# Headlight_Board.net
KiCad netlist of a schematic drawn in Altium Designer
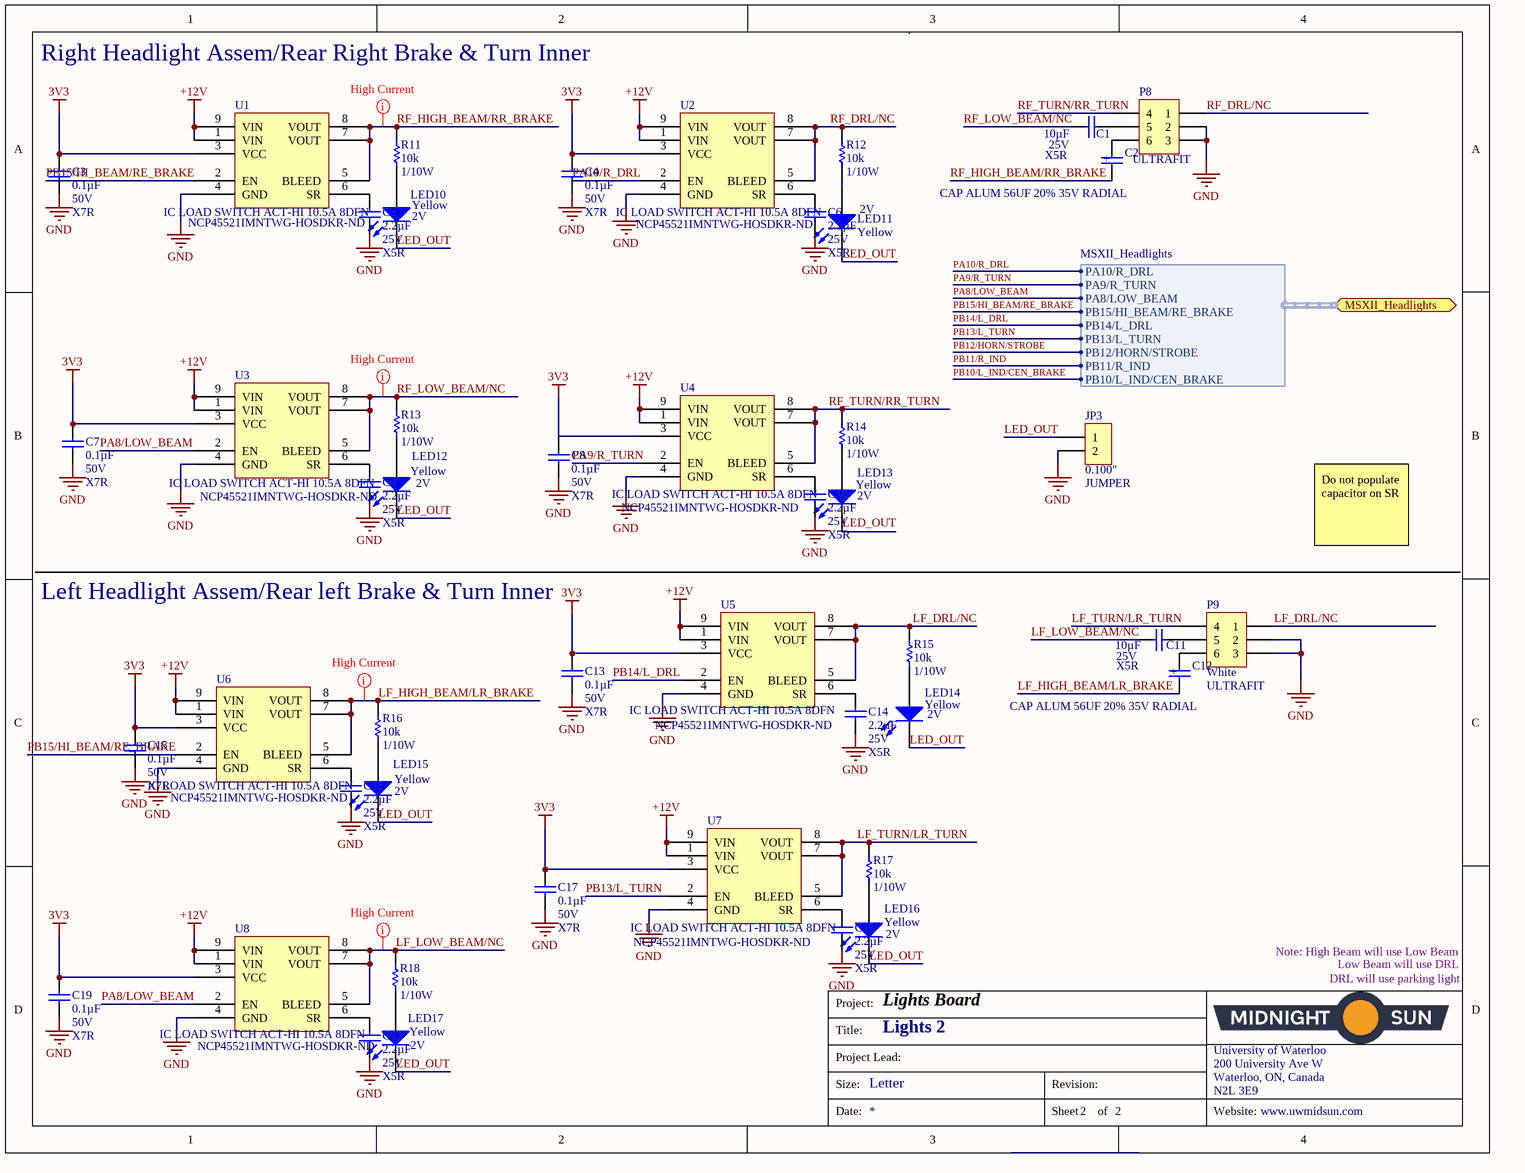
[diagram p0: Headlight_Board.SchDoc]

(export (version "E")
  (design (tool "Eeschema 10.0.6"))
  (components
    (comp (ref "C1")
      (value "CAP CER 10uF 25V 20% X5R 0603")
      (footprint "CAP, 0603")
      (description "10µF ±20% 25V Ceramic Capacitor X5R 0603 (1608 Metric)")
      (fields
        (field (name "TOLERANCE") "±20%")
        (field (name "CAPACITANCE") "10µF")
        (field (name "VOLTAGE") "25V")
        (field (name "TEMPERATURE COEFFICIENT") "X5R")
      )
      (libsource (lib "Schematic Diagrams") (part "CAP CER 10uF 25V 20% X5R 0603"))
    )
    (comp (ref "C2")
      (value "CAP ALUM 56UF 20% 35V RADIAL")
      (footprint "CAP ALUM 56UF 20% 35V RADIAL")
      (description "56µF 35V Aluminum Electrolytic Capacitors Radial, Can 1000 Hrs @ 105°C")
      (fields
        (field (name "MANUFACTURER") "Panasonic Electronic Components")
        (field (name "MANUFACTURER PART NUMBER") "EEU-FC1V560H")
      )
      (libsource (lib "Schematic Diagrams") (part "CAP ALUM 56UF 20% 35V RADIAL"))
    )
    (comp (ref "C3")
      (value "CAP CER 0.1UF 50V 10% X7R 0603")
      (footprint "CAP, 0603")
      (description "0.10µF ±10% 50V Ceramic Capacitor X7R 0603 (1608 Metric)")
      (fields
        (field (name "TOLERANCE") "±10%")
        (field (name "CAPACITANCE") "0.1µF")
        (field (name "VOLTAGE") "50V")
        (field (name "TEMPERATURE COEFFICIENT") "X7R")
      )
      (libsource (lib "Schematic Diagrams") (part "CAP CER 0.1UF 50V 10% X7R 0603"))
    )
    (comp (ref "C4")
      (value "CAP CER 0.1UF 50V 10% X7R 0603")
      (footprint "CAP, 0603")
      (description "0.10µF ±10% 50V Ceramic Capacitor X7R 0603 (1608 Metric)")
      (fields
        (field (name "TOLERANCE") "±10%")
        (field (name "CAPACITANCE") "0.1µF")
        (field (name "VOLTAGE") "50V")
        (field (name "TEMPERATURE COEFFICIENT") "X7R")
      )
      (libsource (lib "Schematic Diagrams") (part "CAP CER 0.1UF 50V 10% X7R 0603"))
    )
    (comp (ref "C5")
      (value "CAP CER 2.2UF 25V 10% X5R 0603")
      (footprint "CAP, 0603")
      (description "2.2µF ±10% 25V Ceramic Capacitor X5R 0603 (1608 Metric)")
      (fields
        (field (name "TOLERANCE") "±10%")
        (field (name "CAPACITANCE") "2.2µF")
        (field (name "VOLTAGE") "25V")
        (field (name "TEMPERATURE COEFFICIENT") "X5R")
      )
      (libsource (lib "Schematic Diagrams") (part "CAP CER 2.2UF 25V 10% X5R 0603"))
    )
    (comp (ref "C6")
      (value "CAP CER 2.2UF 25V 10% X5R 0603")
      (footprint "CAP, 0603")
      (description "2.2µF ±10% 25V Ceramic Capacitor X5R 0603 (1608 Metric)")
      (fields
        (field (name "TOLERANCE") "±10%")
        (field (name "CAPACITANCE") "2.2µF")
        (field (name "VOLTAGE") "25V")
        (field (name "TEMPERATURE COEFFICIENT") "X5R")
      )
      (libsource (lib "Schematic Diagrams") (part "CAP CER 2.2UF 25V 10% X5R 0603"))
    )
    (comp (ref "C7")
      (value "CAP CER 0.1UF 50V 10% X7R 0603")
      (footprint "CAP, 0603")
      (description "0.10µF ±10% 50V Ceramic Capacitor X7R 0603 (1608 Metric)")
      (fields
        (field (name "TOLERANCE") "±10%")
        (field (name "CAPACITANCE") "0.1µF")
        (field (name "VOLTAGE") "50V")
        (field (name "TEMPERATURE COEFFICIENT") "X7R")
      )
      (libsource (lib "Schematic Diagrams") (part "CAP CER 0.1UF 50V 10% X7R 0603"))
    )
    (comp (ref "C8")
      (value "CAP CER 0.1UF 50V 10% X7R 0603")
      (footprint "CAP, 0603")
      (description "0.10µF ±10% 50V Ceramic Capacitor X7R 0603 (1608 Metric)")
      (fields
        (field (name "TOLERANCE") "±10%")
        (field (name "CAPACITANCE") "0.1µF")
        (field (name "VOLTAGE") "50V")
        (field (name "TEMPERATURE COEFFICIENT") "X7R")
      )
      (libsource (lib "Schematic Diagrams") (part "CAP CER 0.1UF 50V 10% X7R 0603"))
    )
    (comp (ref "C9")
      (value "CAP CER 2.2UF 25V 10% X5R 0603")
      (footprint "CAP, 0603")
      (description "2.2µF ±10% 25V Ceramic Capacitor X5R 0603 (1608 Metric)")
      (fields
        (field (name "TOLERANCE") "±10%")
        (field (name "CAPACITANCE") "2.2µF")
        (field (name "VOLTAGE") "25V")
        (field (name "TEMPERATURE COEFFICIENT") "X5R")
      )
      (libsource (lib "Schematic Diagrams") (part "CAP CER 2.2UF 25V 10% X5R 0603"))
    )
    (comp (ref "C10")
      (value "CAP CER 2.2UF 25V 10% X5R 0603")
      (footprint "CAP, 0603")
      (description "2.2µF ±10% 25V Ceramic Capacitor X5R 0603 (1608 Metric)")
      (fields
        (field (name "TOLERANCE") "±10%")
        (field (name "CAPACITANCE") "2.2µF")
        (field (name "VOLTAGE") "25V")
        (field (name "TEMPERATURE COEFFICIENT") "X5R")
      )
      (libsource (lib "Schematic Diagrams") (part "CAP CER 2.2UF 25V 10% X5R 0603"))
    )
    (comp (ref "C11")
      (value "CAP CER 10uF 25V 20% X5R 0603")
      (footprint "CAP, 0603")
      (description "10µF ±20% 25V Ceramic Capacitor X5R 0603 (1608 Metric)")
      (fields
        (field (name "TOLERANCE") "±20%")
        (field (name "CAPACITANCE") "10µF")
        (field (name "VOLTAGE") "25V")
        (field (name "TEMPERATURE COEFFICIENT") "X5R")
      )
      (libsource (lib "Schematic Diagrams") (part "CAP CER 10uF 25V 20% X5R 0603"))
    )
    (comp (ref "C12")
      (value "CAP ALUM 56UF 20% 35V RADIAL")
      (footprint "CAP ALUM 56UF 20% 35V RADIAL")
      (description "56µF 35V Aluminum Electrolytic Capacitors Radial, Can 1000 Hrs @ 105°C")
      (fields
        (field (name "MANUFACTURER") "Panasonic Electronic Components")
        (field (name "MANUFACTURER PART NUMBER") "EEU-FC1V560H")
      )
      (libsource (lib "Schematic Diagrams") (part "CAP ALUM 56UF 20% 35V RADIAL"))
    )
    (comp (ref "C13")
      (value "CAP CER 0.1UF 50V 10% X7R 0603")
      (footprint "CAP, 0603")
      (description "0.10µF ±10% 50V Ceramic Capacitor X7R 0603 (1608 Metric)")
      (fields
        (field (name "TOLERANCE") "±10%")
        (field (name "CAPACITANCE") "0.1µF")
        (field (name "VOLTAGE") "50V")
        (field (name "TEMPERATURE COEFFICIENT") "X7R")
      )
      (libsource (lib "Schematic Diagrams") (part "CAP CER 0.1UF 50V 10% X7R 0603"))
    )
    (comp (ref "C14")
      (value "CAP CER 2.2UF 25V 10% X5R 0603")
      (footprint "CAP, 0603")
      (description "2.2µF ±10% 25V Ceramic Capacitor X5R 0603 (1608 Metric)")
      (fields
        (field (name "TOLERANCE") "±10%")
        (field (name "CAPACITANCE") "2.2µF")
        (field (name "VOLTAGE") "25V")
        (field (name "TEMPERATURE COEFFICIENT") "X5R")
      )
      (libsource (lib "Schematic Diagrams") (part "CAP CER 2.2UF 25V 10% X5R 0603"))
    )
    (comp (ref "C15")
      (value "CAP CER 0.1UF 50V 10% X7R 0603")
      (footprint "CAP, 0603")
      (description "0.10µF ±10% 50V Ceramic Capacitor X7R 0603 (1608 Metric)")
      (fields
        (field (name "TOLERANCE") "±10%")
        (field (name "CAPACITANCE") "0.1µF")
        (field (name "VOLTAGE") "50V")
        (field (name "TEMPERATURE COEFFICIENT") "X7R")
      )
      (libsource (lib "Schematic Diagrams") (part "CAP CER 0.1UF 50V 10% X7R 0603"))
    )
    (comp (ref "C16")
      (value "CAP CER 2.2UF 25V 10% X5R 0603")
      (footprint "CAP, 0603")
      (description "2.2µF ±10% 25V Ceramic Capacitor X5R 0603 (1608 Metric)")
      (fields
        (field (name "TOLERANCE") "±10%")
        (field (name "CAPACITANCE") "2.2µF")
        (field (name "VOLTAGE") "25V")
        (field (name "TEMPERATURE COEFFICIENT") "X5R")
      )
      (libsource (lib "Schematic Diagrams") (part "CAP CER 2.2UF 25V 10% X5R 0603"))
    )
    (comp (ref "C17")
      (value "CAP CER 0.1UF 50V 10% X7R 0603")
      (footprint "CAP, 0603")
      (description "0.10µF ±10% 50V Ceramic Capacitor X7R 0603 (1608 Metric)")
      (fields
        (field (name "TOLERANCE") "±10%")
        (field (name "CAPACITANCE") "0.1µF")
        (field (name "VOLTAGE") "50V")
        (field (name "TEMPERATURE COEFFICIENT") "X7R")
      )
      (libsource (lib "Schematic Diagrams") (part "CAP CER 0.1UF 50V 10% X7R 0603"))
    )
    (comp (ref "C18")
      (value "CAP CER 2.2UF 25V 10% X5R 0603")
      (footprint "CAP, 0603")
      (description "2.2µF ±10% 25V Ceramic Capacitor X5R 0603 (1608 Metric)")
      (fields
        (field (name "TOLERANCE") "±10%")
        (field (name "CAPACITANCE") "2.2µF")
        (field (name "VOLTAGE") "25V")
        (field (name "TEMPERATURE COEFFICIENT") "X5R")
      )
      (libsource (lib "Schematic Diagrams") (part "CAP CER 2.2UF 25V 10% X5R 0603"))
    )
    (comp (ref "C19")
      (value "CAP CER 0.1UF 50V 10% X7R 0603")
      (footprint "CAP, 0603")
      (description "0.10µF ±10% 50V Ceramic Capacitor X7R 0603 (1608 Metric)")
      (fields
        (field (name "TOLERANCE") "±10%")
        (field (name "CAPACITANCE") "0.1µF")
        (field (name "VOLTAGE") "50V")
        (field (name "TEMPERATURE COEFFICIENT") "X7R")
      )
      (libsource (lib "Schematic Diagrams") (part "CAP CER 0.1UF 50V 10% X7R 0603"))
    )
    (comp (ref "C20")
      (value "CAP CER 2.2UF 25V 10% X5R 0603")
      (footprint "CAP, 0603")
      (description "2.2µF ±10% 25V Ceramic Capacitor X5R 0603 (1608 Metric)")
      (fields
        (field (name "TOLERANCE") "±10%")
        (field (name "CAPACITANCE") "2.2µF")
        (field (name "VOLTAGE") "25V")
        (field (name "TEMPERATURE COEFFICIENT") "X5R")
      )
      (libsource (lib "Schematic Diagrams") (part "CAP CER 2.2UF 25V 10% X5R 0603"))
    )
    (comp (ref "JP3")
      (value "JUMPER")
      (footprint "CONN 2POS JUMPER 0.1\"")
      (description "2 Positions Header Connector Through Hole Gold")
      (fields
        (field (name "MANUFACTURER") "Omron Electronics Inc-EMC Div")
        (field (name "MANUFACTURER PART NUMBER") "XG8T-0231")
        (field (name "ROW SPACING - MATING") "0.100\"")
        (field (name "TYPE") "JUMPER")
      )
      (libsource (lib "Schematic Diagrams") (part "CONN 2POS JUMPER 0.1{dblquote}"))
    )
    (comp (ref "LED10")
      (value "LED YELLOW CLEAR 2.1V 0603")
      (footprint "LED_0603")
      (description "Yellow 590nm LED Indication - Discrete 2V 0603 (1608 Metric)")
      (fields
        (field (name "MANUFACTURER") "Wurth Electronics Inc.")
        (field (name "MANUFACTURER PART NUMBER") "150060YS75000")
        (field (name "COLOR") "Yellow")
        (field (name "VOLTAGE - FORWARD (VF) (TYP)") "2V")
      )
      (libsource (lib "Schematic Diagrams") (part "LED YELLOW CLEAR 2.1V 0603"))
    )
    (comp (ref "LED11")
      (value "LED YELLOW CLEAR 2.1V 0603")
      (footprint "LED_0603")
      (description "Yellow 590nm LED Indication - Discrete 2V 0603 (1608 Metric)")
      (fields
        (field (name "MANUFACTURER") "Wurth Electronics Inc.")
        (field (name "MANUFACTURER PART NUMBER") "150060YS75000")
        (field (name "COLOR") "Yellow")
        (field (name "VOLTAGE - FORWARD (VF) (TYP)") "2V")
      )
      (libsource (lib "Schematic Diagrams") (part "LED YELLOW CLEAR 2.1V 0603"))
    )
    (comp (ref "LED12")
      (value "LED YELLOW CLEAR 2.1V 0603")
      (footprint "LED_0603")
      (description "Yellow 590nm LED Indication - Discrete 2V 0603 (1608 Metric)")
      (fields
        (field (name "MANUFACTURER") "Wurth Electronics Inc.")
        (field (name "MANUFACTURER PART NUMBER") "150060YS75000")
        (field (name "COLOR") "Yellow")
        (field (name "VOLTAGE - FORWARD (VF) (TYP)") "2V")
      )
      (libsource (lib "Schematic Diagrams") (part "LED YELLOW CLEAR 2.1V 0603"))
    )
    (comp (ref "LED13")
      (value "LED YELLOW CLEAR 2.1V 0603")
      (footprint "LED_0603")
      (description "Yellow 590nm LED Indication - Discrete 2V 0603 (1608 Metric)")
      (fields
        (field (name "MANUFACTURER") "Wurth Electronics Inc.")
        (field (name "MANUFACTURER PART NUMBER") "150060YS75000")
        (field (name "COLOR") "Yellow")
        (field (name "VOLTAGE - FORWARD (VF) (TYP)") "2V")
      )
      (libsource (lib "Schematic Diagrams") (part "LED YELLOW CLEAR 2.1V 0603"))
    )
    (comp (ref "LED14")
      (value "LED YELLOW CLEAR 2.1V 0603")
      (footprint "LED_0603")
      (description "Yellow 590nm LED Indication - Discrete 2V 0603 (1608 Metric)")
      (fields
        (field (name "MANUFACTURER") "Wurth Electronics Inc.")
        (field (name "MANUFACTURER PART NUMBER") "150060YS75000")
        (field (name "COLOR") "Yellow")
        (field (name "VOLTAGE - FORWARD (VF) (TYP)") "2V")
      )
      (libsource (lib "Schematic Diagrams") (part "LED YELLOW CLEAR 2.1V 0603"))
    )
    (comp (ref "LED15")
      (value "LED YELLOW CLEAR 2.1V 0603")
      (footprint "LED_0603")
      (description "Yellow 590nm LED Indication - Discrete 2V 0603 (1608 Metric)")
      (fields
        (field (name "MANUFACTURER") "Wurth Electronics Inc.")
        (field (name "MANUFACTURER PART NUMBER") "150060YS75000")
        (field (name "COLOR") "Yellow")
        (field (name "VOLTAGE - FORWARD (VF) (TYP)") "2V")
      )
      (libsource (lib "Schematic Diagrams") (part "LED YELLOW CLEAR 2.1V 0603"))
    )
    (comp (ref "LED16")
      (value "LED YELLOW CLEAR 2.1V 0603")
      (footprint "LED_0603")
      (description "Yellow 590nm LED Indication - Discrete 2V 0603 (1608 Metric)")
      (fields
        (field (name "MANUFACTURER") "Wurth Electronics Inc.")
        (field (name "MANUFACTURER PART NUMBER") "150060YS75000")
        (field (name "COLOR") "Yellow")
        (field (name "VOLTAGE - FORWARD (VF) (TYP)") "2V")
      )
      (libsource (lib "Schematic Diagrams") (part "LED YELLOW CLEAR 2.1V 0603"))
    )
    (comp (ref "LED17")
      (value "LED YELLOW CLEAR 2.1V 0603")
      (footprint "LED_0603")
      (description "Yellow 590nm LED Indication - Discrete 2V 0603 (1608 Metric)")
      (fields
        (field (name "MANUFACTURER") "Wurth Electronics Inc.")
        (field (name "MANUFACTURER PART NUMBER") "150060YS75000")
        (field (name "COLOR") "Yellow")
        (field (name "VOLTAGE - FORWARD (VF) (TYP)") "2V")
      )
      (libsource (lib "Schematic Diagrams") (part "LED YELLOW CLEAR 2.1V 0603"))
    )
    (comp (ref "P8")
      (value "CONN 6POS ULTRA-FIT 0.138\"")
      (footprint "CONN, 6POS ULTRA-FIT")
      (description "6 Positions Header Connector 0.138\" (3.50mm) Through Hole Tin")
      (fields (field (name "VOLTAGE") "400V") (field (name "SERIES") "ULTRAFIT"))
      (libsource (lib "Schematic Diagrams") (part "CONN 6POS ULTRA-FIT 0.138{dblquote}"))
    )
    (comp (ref "P9")
      (value "CONN 6POS ULTRA-FIT NATURAL COLOR 0.138\"")
      (footprint "CONN, 6POS ULTRA-FIT - NATURAL COLOR")
      (description "6 Positions Header Connector 0.138\" (3.50mm) Through Hole Tin")
      (fields (field (name "INSULATION COLOR") "White") (field (name "SERIES") "ULTRAFIT"))
      (libsource (lib "Schematic Diagrams") (part "CONN 6POS ULTRA-FIT NATURAL COLOR 0.138{dblquote}"))
    )
    (comp (ref "R11")
      (value "RES 10K OHM 1% 1/10W 0603")
      (footprint "RES, 0603")
      (description "RES SMD 10K OHM 1% 1/10W 0603")
      (fields
        (field (name "TOLERANCE") "±1%")
        (field (name "RESISTANCE") "10k")
        (field (name "POWER") "1/10W")
      )
      (libsource (lib "Schematic Diagrams") (part "RES 10K OHM 1% 1/10W 0603"))
    )
    (comp (ref "R12")
      (value "RES 10K OHM 1% 1/10W 0603")
      (footprint "RES, 0603")
      (description "RES SMD 10K OHM 1% 1/10W 0603")
      (fields
        (field (name "TOLERANCE") "±1%")
        (field (name "RESISTANCE") "10k")
        (field (name "POWER") "1/10W")
      )
      (libsource (lib "Schematic Diagrams") (part "RES 10K OHM 1% 1/10W 0603"))
    )
    (comp (ref "R13")
      (value "RES 10K OHM 1% 1/10W 0603")
      (footprint "RES, 0603")
      (description "RES SMD 10K OHM 1% 1/10W 0603")
      (fields
        (field (name "TOLERANCE") "±1%")
        (field (name "RESISTANCE") "10k")
        (field (name "POWER") "1/10W")
      )
      (libsource (lib "Schematic Diagrams") (part "RES 10K OHM 1% 1/10W 0603"))
    )
    (comp (ref "R14")
      (value "RES 10K OHM 1% 1/10W 0603")
      (footprint "RES, 0603")
      (description "RES SMD 10K OHM 1% 1/10W 0603")
      (fields
        (field (name "TOLERANCE") "±1%")
        (field (name "RESISTANCE") "10k")
        (field (name "POWER") "1/10W")
      )
      (libsource (lib "Schematic Diagrams") (part "RES 10K OHM 1% 1/10W 0603"))
    )
    (comp (ref "R15")
      (value "RES 10K OHM 1% 1/10W 0603")
      (footprint "RES, 0603")
      (description "RES SMD 10K OHM 1% 1/10W 0603")
      (fields
        (field (name "TOLERANCE") "±1%")
        (field (name "RESISTANCE") "10k")
        (field (name "POWER") "1/10W")
      )
      (libsource (lib "Schematic Diagrams") (part "RES 10K OHM 1% 1/10W 0603"))
    )
    (comp (ref "R16")
      (value "RES 10K OHM 1% 1/10W 0603")
      (footprint "RES, 0603")
      (description "RES SMD 10K OHM 1% 1/10W 0603")
      (fields
        (field (name "TOLERANCE") "±1%")
        (field (name "RESISTANCE") "10k")
        (field (name "POWER") "1/10W")
      )
      (libsource (lib "Schematic Diagrams") (part "RES 10K OHM 1% 1/10W 0603"))
    )
    (comp (ref "R17")
      (value "RES 10K OHM 1% 1/10W 0603")
      (footprint "RES, 0603")
      (description "RES SMD 10K OHM 1% 1/10W 0603")
      (fields
        (field (name "TOLERANCE") "±1%")
        (field (name "RESISTANCE") "10k")
        (field (name "POWER") "1/10W")
      )
      (libsource (lib "Schematic Diagrams") (part "RES 10K OHM 1% 1/10W 0603"))
    )
    (comp (ref "R18")
      (value "RES 10K OHM 1% 1/10W 0603")
      (footprint "RES, 0603")
      (description "RES SMD 10K OHM 1% 1/10W 0603")
      (fields
        (field (name "TOLERANCE") "±1%")
        (field (name "RESISTANCE") "10k")
        (field (name "POWER") "1/10W")
      )
      (libsource (lib "Schematic Diagrams") (part "RES 10K OHM 1% 1/10W 0603"))
    )
    (comp (ref "U1")
      (value "IC LOAD SWITCH ACT-HI 10.5A 8DFN")
      (footprint "IC LOAD SWITCH ACT-HI 10.5A 8DFN")
      (description "NCP45521IMNTWG-H")
      (fields
        (field (name "MANUFACTURER") "ON Semiconductor")
        (field (name "SUPPLIER PART NUMBER 2") "NCP45521IMNTWG-HOSDKR-ND")
      )
      (libsource (lib "Schematic Diagrams") (part "IC LOAD SWITCH ACT-HI 10.5A 8DFN"))
    )
    (comp (ref "U2")
      (value "IC LOAD SWITCH ACT-HI 10.5A 8DFN")
      (footprint "IC LOAD SWITCH ACT-HI 10.5A 8DFN")
      (description "NCP45521IMNTWG-H")
      (fields
        (field (name "MANUFACTURER") "ON Semiconductor")
        (field (name "SUPPLIER PART NUMBER 2") "NCP45521IMNTWG-HOSDKR-ND")
      )
      (libsource (lib "Schematic Diagrams") (part "IC LOAD SWITCH ACT-HI 10.5A 8DFN"))
    )
    (comp (ref "U3")
      (value "IC LOAD SWITCH ACT-HI 10.5A 8DFN")
      (footprint "IC LOAD SWITCH ACT-HI 10.5A 8DFN")
      (description "NCP45521IMNTWG-H")
      (fields
        (field (name "MANUFACTURER") "ON Semiconductor")
        (field (name "SUPPLIER PART NUMBER 2") "NCP45521IMNTWG-HOSDKR-ND")
      )
      (libsource (lib "Schematic Diagrams") (part "IC LOAD SWITCH ACT-HI 10.5A 8DFN"))
    )
    (comp (ref "U4")
      (value "IC LOAD SWITCH ACT-HI 10.5A 8DFN")
      (footprint "IC LOAD SWITCH ACT-HI 10.5A 8DFN")
      (description "NCP45521IMNTWG-H")
      (fields
        (field (name "MANUFACTURER") "ON Semiconductor")
        (field (name "SUPPLIER PART NUMBER 2") "NCP45521IMNTWG-HOSDKR-ND")
      )
      (libsource (lib "Schematic Diagrams") (part "IC LOAD SWITCH ACT-HI 10.5A 8DFN"))
    )
    (comp (ref "U5")
      (value "IC LOAD SWITCH ACT-HI 10.5A 8DFN")
      (footprint "IC LOAD SWITCH ACT-HI 10.5A 8DFN")
      (description "NCP45521IMNTWG-H")
      (fields
        (field (name "MANUFACTURER") "ON Semiconductor")
        (field (name "SUPPLIER PART NUMBER 2") "NCP45521IMNTWG-HOSDKR-ND")
      )
      (libsource (lib "Schematic Diagrams") (part "IC LOAD SWITCH ACT-HI 10.5A 8DFN"))
    )
    (comp (ref "U6")
      (value "IC LOAD SWITCH ACT-HI 10.5A 8DFN")
      (footprint "IC LOAD SWITCH ACT-HI 10.5A 8DFN")
      (description "NCP45521IMNTWG-H")
      (fields
        (field (name "MANUFACTURER") "ON Semiconductor")
        (field (name "SUPPLIER PART NUMBER 2") "NCP45521IMNTWG-HOSDKR-ND")
      )
      (libsource (lib "Schematic Diagrams") (part "IC LOAD SWITCH ACT-HI 10.5A 8DFN"))
    )
    (comp (ref "U7")
      (value "IC LOAD SWITCH ACT-HI 10.5A 8DFN")
      (footprint "IC LOAD SWITCH ACT-HI 10.5A 8DFN")
      (description "NCP45521IMNTWG-H")
      (fields
        (field (name "MANUFACTURER") "ON Semiconductor")
        (field (name "SUPPLIER PART NUMBER 2") "NCP45521IMNTWG-HOSDKR-ND")
      )
      (libsource (lib "Schematic Diagrams") (part "IC LOAD SWITCH ACT-HI 10.5A 8DFN"))
    )
    (comp (ref "U8")
      (value "IC LOAD SWITCH ACT-HI 10.5A 8DFN")
      (footprint "IC LOAD SWITCH ACT-HI 10.5A 8DFN")
      (description "NCP45521IMNTWG-H")
      (fields
        (field (name "MANUFACTURER") "ON Semiconductor")
        (field (name "SUPPLIER PART NUMBER 2") "NCP45521IMNTWG-HOSDKR-ND")
      )
      (libsource (lib "Schematic Diagrams") (part "IC LOAD SWITCH ACT-HI 10.5A 8DFN"))
    )
  )
  (nets
    (net (code "2") (name "+12V") (class "Default")
      (node (ref "U1") (pin "1") (pinfunction "VIN_1") (pintype "passive"))
      (node (ref "U1") (pin "9") (pinfunction "VIN_9") (pintype "passive"))
      (node (ref "U2") (pin "1") (pinfunction "VIN_1") (pintype "passive"))
      (node (ref "U2") (pin "9") (pinfunction "VIN_9") (pintype "passive"))
      (node (ref "U3") (pin "1") (pinfunction "VIN_1") (pintype "passive"))
      (node (ref "U3") (pin "9") (pinfunction "VIN_9") (pintype "passive"))
      (node (ref "U4") (pin "1") (pinfunction "VIN_1") (pintype "passive"))
      (node (ref "U4") (pin "9") (pinfunction "VIN_9") (pintype "passive"))
      (node (ref "U5") (pin "1") (pinfunction "VIN_1") (pintype "passive"))
      (node (ref "U5") (pin "9") (pinfunction "VIN_9") (pintype "passive"))
      (node (ref "U6") (pin "1") (pinfunction "VIN_1") (pintype "passive"))
      (node (ref "U6") (pin "9") (pinfunction "VIN_9") (pintype "passive"))
      (node (ref "U7") (pin "1") (pinfunction "VIN_1") (pintype "passive"))
      (node (ref "U7") (pin "9") (pinfunction "VIN_9") (pintype "passive"))
      (node (ref "U8") (pin "1") (pinfunction "VIN_1") (pintype "passive"))
      (node (ref "U8") (pin "9") (pinfunction "VIN_9") (pintype "passive"))
    )
    (net (code "3") (name "/LED_OUT") (class "Default")
      (node (ref "JP3") (pin "1") (pinfunction "1_1") (pintype "passive"))
      (node (ref "LED10") (pin "2") (pinfunction "K_2") (pintype "passive"))
      (node (ref "LED11") (pin "2") (pinfunction "K_2") (pintype "passive"))
      (node (ref "LED12") (pin "2") (pinfunction "K_2") (pintype "passive"))
      (node (ref "LED13") (pin "2") (pinfunction "K_2") (pintype "passive"))
      (node (ref "LED14") (pin "2") (pinfunction "K_2") (pintype "passive"))
      (node (ref "LED15") (pin "2") (pinfunction "K_2") (pintype "passive"))
      (node (ref "LED16") (pin "2") (pinfunction "K_2") (pintype "passive"))
      (node (ref "LED17") (pin "2") (pinfunction "K_2") (pintype "passive"))
    )
    (net (code "4") (name "/LF_DRL{slash}NC") (class "Default")
      (node (ref "P9") (pin "1") (pinfunction "1_1") (pintype "passive"))
      (node (ref "R15") (pin "1") (pinfunction "1_1") (pintype "passive"))
      (node (ref "U5") (pin "5") (pinfunction "BLEED_5") (pintype "passive"))
      (node (ref "U5") (pin "7") (pinfunction "VOUT_7") (pintype "passive"))
      (node (ref "U5") (pin "8") (pinfunction "VOUT_8") (pintype "passive"))
    )
    (net (code "5") (name "/LF_HIGH_BEAM{slash}LR_BRAKE") (class "Default")
      (node (ref "C12") (pin "2") (pinfunction "2_2") (pintype "passive"))
      (node (ref "R16") (pin "1") (pinfunction "1_1") (pintype "passive"))
      (node (ref "U6") (pin "5") (pinfunction "BLEED_5") (pintype "passive"))
      (node (ref "U6") (pin "7") (pinfunction "VOUT_7") (pintype "passive"))
      (node (ref "U6") (pin "8") (pinfunction "VOUT_8") (pintype "passive"))
    )
    (net (code "6") (name "/LF_LOW_BEAM{slash}NC") (class "Default")
      (node (ref "C11") (pin "2") (pinfunction "2_2") (pintype "passive"))
      (node (ref "R18") (pin "1") (pinfunction "1_1") (pintype "passive"))
      (node (ref "U8") (pin "5") (pinfunction "BLEED_5") (pintype "passive"))
      (node (ref "U8") (pin "7") (pinfunction "VOUT_7") (pintype "passive"))
      (node (ref "U8") (pin "8") (pinfunction "VOUT_8") (pintype "passive"))
    )
    (net (code "7") (name "/LF_TURN{slash}LR_TURN") (class "Default")
      (node (ref "P9") (pin "4") (pinfunction "4_4") (pintype "passive"))
      (node (ref "R17") (pin "1") (pinfunction "1_1") (pintype "passive"))
      (node (ref "U7") (pin "5") (pinfunction "BLEED_5") (pintype "passive"))
      (node (ref "U7") (pin "7") (pinfunction "VOUT_7") (pintype "passive"))
      (node (ref "U7") (pin "8") (pinfunction "VOUT_8") (pintype "passive"))
    )
    (net (code "8") (name "/PA8{slash}LOW_BEAM") (class "Default")
      (node (ref "U3") (pin "2") (pinfunction "EN_2") (pintype "passive"))
      (node (ref "U8") (pin "2") (pinfunction "EN_2") (pintype "passive"))
    )
    (net (code "9") (name "/PA9{slash}R_TURN") (class "Default")
      (node (ref "U4") (pin "2") (pinfunction "EN_2") (pintype "passive"))
    )
    (net (code "10") (name "/PA10{slash}R_DRL") (class "Default")
      (node (ref "U2") (pin "2") (pinfunction "EN_2") (pintype "passive"))
    )
    (net (code "14") (name "/PB13{slash}L_TURN") (class "Default")
      (node (ref "U7") (pin "2") (pinfunction "EN_2") (pintype "passive"))
    )
    (net (code "15") (name "/PB14{slash}L_DRL") (class "Default")
      (node (ref "U5") (pin "2") (pinfunction "EN_2") (pintype "passive"))
    )
    (net (code "16") (name "/PB15{slash}HI_BEAM{slash}RE_BRAKE") (class "Default")
      (node (ref "U1") (pin "2") (pinfunction "EN_2") (pintype "passive"))
      (node (ref "U6") (pin "2") (pinfunction "EN_2") (pintype "passive"))
    )
    (net (code "17") (name "/RF_DRL{slash}NC") (class "Default")
      (node (ref "P8") (pin "1") (pinfunction "1_1") (pintype "passive"))
      (node (ref "R12") (pin "1") (pinfunction "1_1") (pintype "passive"))
      (node (ref "U2") (pin "5") (pinfunction "BLEED_5") (pintype "passive"))
      (node (ref "U2") (pin "7") (pinfunction "VOUT_7") (pintype "passive"))
      (node (ref "U2") (pin "8") (pinfunction "VOUT_8") (pintype "passive"))
    )
    (net (code "18") (name "/RF_HIGH_BEAM{slash}RR_BRAKE") (class "Default")
      (node (ref "C2") (pin "2") (pinfunction "2_2") (pintype "passive"))
      (node (ref "R11") (pin "1") (pinfunction "1_1") (pintype "passive"))
      (node (ref "U1") (pin "5") (pinfunction "BLEED_5") (pintype "passive"))
      (node (ref "U1") (pin "7") (pinfunction "VOUT_7") (pintype "passive"))
      (node (ref "U1") (pin "8") (pinfunction "VOUT_8") (pintype "passive"))
    )
    (net (code "19") (name "/RF_LOW_BEAM{slash}NC") (class "Default")
      (node (ref "C1") (pin "2") (pinfunction "2_2") (pintype "passive"))
      (node (ref "R13") (pin "1") (pinfunction "1_1") (pintype "passive"))
      (node (ref "U3") (pin "5") (pinfunction "BLEED_5") (pintype "passive"))
      (node (ref "U3") (pin "7") (pinfunction "VOUT_7") (pintype "passive"))
      (node (ref "U3") (pin "8") (pinfunction "VOUT_8") (pintype "passive"))
    )
    (net (code "20") (name "/RF_TURN{slash}RR_TURN") (class "Default")
      (node (ref "P8") (pin "4") (pinfunction "4_4") (pintype "passive"))
      (node (ref "R14") (pin "1") (pinfunction "1_1") (pintype "passive"))
      (node (ref "U4") (pin "5") (pinfunction "BLEED_5") (pintype "passive"))
      (node (ref "U4") (pin "7") (pinfunction "VOUT_7") (pintype "passive"))
      (node (ref "U4") (pin "8") (pinfunction "VOUT_8") (pintype "passive"))
    )
    (net (code "22") (name "3V3") (class "Default")
      (node (ref "C13") (pin "1") (pinfunction "1_1") (pintype "passive"))
      (node (ref "C15") (pin "1") (pinfunction "1_1") (pintype "passive"))
      (node (ref "C17") (pin "1") (pinfunction "1_1") (pintype "passive"))
      (node (ref "C19") (pin "1") (pinfunction "1_1") (pintype "passive"))
      (node (ref "C3") (pin "1") (pinfunction "1_1") (pintype "passive"))
      (node (ref "C4") (pin "1") (pinfunction "1_1") (pintype "passive"))
      (node (ref "C7") (pin "1") (pinfunction "1_1") (pintype "passive"))
      (node (ref "U1") (pin "3") (pinfunction "VCC_3") (pintype "passive"))
      (node (ref "U2") (pin "3") (pinfunction "VCC_3") (pintype "passive"))
      (node (ref "U3") (pin "3") (pinfunction "VCC_3") (pintype "passive"))
      (node (ref "U4") (pin "3") (pinfunction "VCC_3") (pintype "passive"))
      (node (ref "U5") (pin "3") (pinfunction "VCC_3") (pintype "passive"))
      (node (ref "U6") (pin "3") (pinfunction "VCC_3") (pintype "passive"))
      (node (ref "U7") (pin "3") (pinfunction "VCC_3") (pintype "passive"))
      (node (ref "U8") (pin "3") (pinfunction "VCC_3") (pintype "passive"))
    )
    (net (code "23") (name "GND") (class "Default")
      (node (ref "C10") (pin "2") (pinfunction "2_2") (pintype "passive"))
      (node (ref "C13") (pin "2") (pinfunction "2_2") (pintype "passive"))
      (node (ref "C14") (pin "2") (pinfunction "2_2") (pintype "passive"))
      (node (ref "C15") (pin "2") (pinfunction "2_2") (pintype "passive"))
      (node (ref "C16") (pin "2") (pinfunction "2_2") (pintype "passive"))
      (node (ref "C17") (pin "2") (pinfunction "2_2") (pintype "passive"))
      (node (ref "C18") (pin "2") (pinfunction "2_2") (pintype "passive"))
      (node (ref "C19") (pin "2") (pinfunction "2_2") (pintype "passive"))
      (node (ref "C20") (pin "2") (pinfunction "2_2") (pintype "passive"))
      (node (ref "C3") (pin "2") (pinfunction "2_2") (pintype "passive"))
      (node (ref "C4") (pin "2") (pinfunction "2_2") (pintype "passive"))
      (node (ref "C5") (pin "2") (pinfunction "2_2") (pintype "passive"))
      (node (ref "C6") (pin "2") (pinfunction "2_2") (pintype "passive"))
      (node (ref "C7") (pin "2") (pinfunction "2_2") (pintype "passive"))
      (node (ref "C8") (pin "2") (pinfunction "2_2") (pintype "passive"))
      (node (ref "C9") (pin "2") (pinfunction "2_2") (pintype "passive"))
      (node (ref "JP3") (pin "2") (pinfunction "2_2") (pintype "passive"))
      (node (ref "P8") (pin "2") (pinfunction "2_2") (pintype "passive"))
      (node (ref "P8") (pin "3") (pinfunction "3_3") (pintype "passive"))
      (node (ref "P9") (pin "2") (pinfunction "2_2") (pintype "passive"))
      (node (ref "P9") (pin "3") (pinfunction "3_3") (pintype "passive"))
      (node (ref "U1") (pin "4") (pinfunction "GND_4") (pintype "passive"))
      (node (ref "U2") (pin "4") (pinfunction "GND_4") (pintype "passive"))
      (node (ref "U3") (pin "4") (pinfunction "GND_4") (pintype "passive"))
      (node (ref "U4") (pin "4") (pinfunction "GND_4") (pintype "passive"))
      (node (ref "U5") (pin "4") (pinfunction "GND_4") (pintype "passive"))
      (node (ref "U6") (pin "4") (pinfunction "GND_4") (pintype "passive"))
      (node (ref "U7") (pin "4") (pinfunction "GND_4") (pintype "passive"))
      (node (ref "U8") (pin "4") (pinfunction "GND_4") (pintype "passive"))
    )
    (net (code "24") (name "Net-(C1-Pad1)") (class "Default")
      (node (ref "C1") (pin "1") (pinfunction "1_1") (pintype "passive"))
      (node (ref "P8") (pin "5") (pinfunction "5_5") (pintype "passive"))
    )
    (net (code "25") (name "Net-(C2-Pad1)") (class "Default")
      (node (ref "C2") (pin "1") (pinfunction "1_1") (pintype "passive"))
      (node (ref "P8") (pin "6") (pinfunction "6_6") (pintype "passive"))
    )
    (net (code "26") (name "Net-(C11-Pad1)") (class "Default")
      (node (ref "C11") (pin "1") (pinfunction "1_1") (pintype "passive"))
      (node (ref "P9") (pin "5") (pinfunction "5_5") (pintype "passive"))
    )
    (net (code "27") (name "Net-(C12-Pad1)") (class "Default")
      (node (ref "C12") (pin "1") (pinfunction "1_1") (pintype "passive"))
      (node (ref "P9") (pin "6") (pinfunction "6_6") (pintype "passive"))
    )
    (net (code "28") (name "Net-(LED10-A)") (class "Default")
      (node (ref "LED10") (pin "1") (pinfunction "A_1") (pintype "passive"))
      (node (ref "R11") (pin "2") (pinfunction "2_2") (pintype "passive"))
    )
    (net (code "29") (name "Net-(LED11-A)") (class "Default")
      (node (ref "LED11") (pin "1") (pinfunction "A_1") (pintype "passive"))
      (node (ref "R12") (pin "2") (pinfunction "2_2") (pintype "passive"))
    )
    (net (code "30") (name "Net-(LED12-A)") (class "Default")
      (node (ref "LED12") (pin "1") (pinfunction "A_1") (pintype "passive"))
      (node (ref "R13") (pin "2") (pinfunction "2_2") (pintype "passive"))
    )
    (net (code "31") (name "Net-(LED13-A)") (class "Default")
      (node (ref "LED13") (pin "1") (pinfunction "A_1") (pintype "passive"))
      (node (ref "R14") (pin "2") (pinfunction "2_2") (pintype "passive"))
    )
    (net (code "32") (name "Net-(LED14-A)") (class "Default")
      (node (ref "LED14") (pin "1") (pinfunction "A_1") (pintype "passive"))
      (node (ref "R15") (pin "2") (pinfunction "2_2") (pintype "passive"))
    )
    (net (code "33") (name "Net-(LED15-A)") (class "Default")
      (node (ref "LED15") (pin "1") (pinfunction "A_1") (pintype "passive"))
      (node (ref "R16") (pin "2") (pinfunction "2_2") (pintype "passive"))
    )
    (net (code "34") (name "Net-(LED16-A)") (class "Default")
      (node (ref "LED16") (pin "1") (pinfunction "A_1") (pintype "passive"))
      (node (ref "R17") (pin "2") (pinfunction "2_2") (pintype "passive"))
    )
    (net (code "35") (name "Net-(LED17-A)") (class "Default")
      (node (ref "LED17") (pin "1") (pinfunction "A_1") (pintype "passive"))
      (node (ref "R18") (pin "2") (pinfunction "2_2") (pintype "passive"))
    )
    (net (code "36") (name "Net-(U1-SR)") (class "Default")
      (node (ref "C5") (pin "1") (pinfunction "1_1") (pintype "passive"))
      (node (ref "U1") (pin "6") (pinfunction "SR_6") (pintype "passive"))
    )
    (net (code "37") (name "Net-(U2-SR)") (class "Default")
      (node (ref "C6") (pin "1") (pinfunction "1_1") (pintype "passive"))
      (node (ref "U2") (pin "6") (pinfunction "SR_6") (pintype "passive"))
    )
    (net (code "38") (name "Net-(U3-SR)") (class "Default")
      (node (ref "C9") (pin "1") (pinfunction "1_1") (pintype "passive"))
      (node (ref "U3") (pin "6") (pinfunction "SR_6") (pintype "passive"))
    )
    (net (code "39") (name "Net-(U4-SR)") (class "Default")
      (node (ref "C10") (pin "1") (pinfunction "1_1") (pintype "passive"))
      (node (ref "U4") (pin "6") (pinfunction "SR_6") (pintype "passive"))
    )
    (net (code "40") (name "Net-(U5-SR)") (class "Default")
      (node (ref "C14") (pin "1") (pinfunction "1_1") (pintype "passive"))
      (node (ref "U5") (pin "6") (pinfunction "SR_6") (pintype "passive"))
    )
    (net (code "41") (name "Net-(U6-SR)") (class "Default")
      (node (ref "C16") (pin "1") (pinfunction "1_1") (pintype "passive"))
      (node (ref "U6") (pin "6") (pinfunction "SR_6") (pintype "passive"))
    )
    (net (code "42") (name "Net-(U7-SR)") (class "Default")
      (node (ref "C18") (pin "1") (pinfunction "1_1") (pintype "passive"))
      (node (ref "U7") (pin "6") (pinfunction "SR_6") (pintype "passive"))
    )
    (net (code "43") (name "Net-(U8-SR)") (class "Default")
      (node (ref "C20") (pin "1") (pinfunction "1_1") (pintype "passive"))
      (node (ref "U8") (pin "6") (pinfunction "SR_6") (pintype "passive"))
    )
    (net (code "44") (name "unconnected-(C8-Pad1)") (class "Default")
      (node (ref "C8") (pin "1") (pinfunction "1_1") (pintype "passive"))
    )
  )
)
